# Chime_PCB_v2_8_11_17.net
KiCad netlist of a schematic drawn in EAGLE
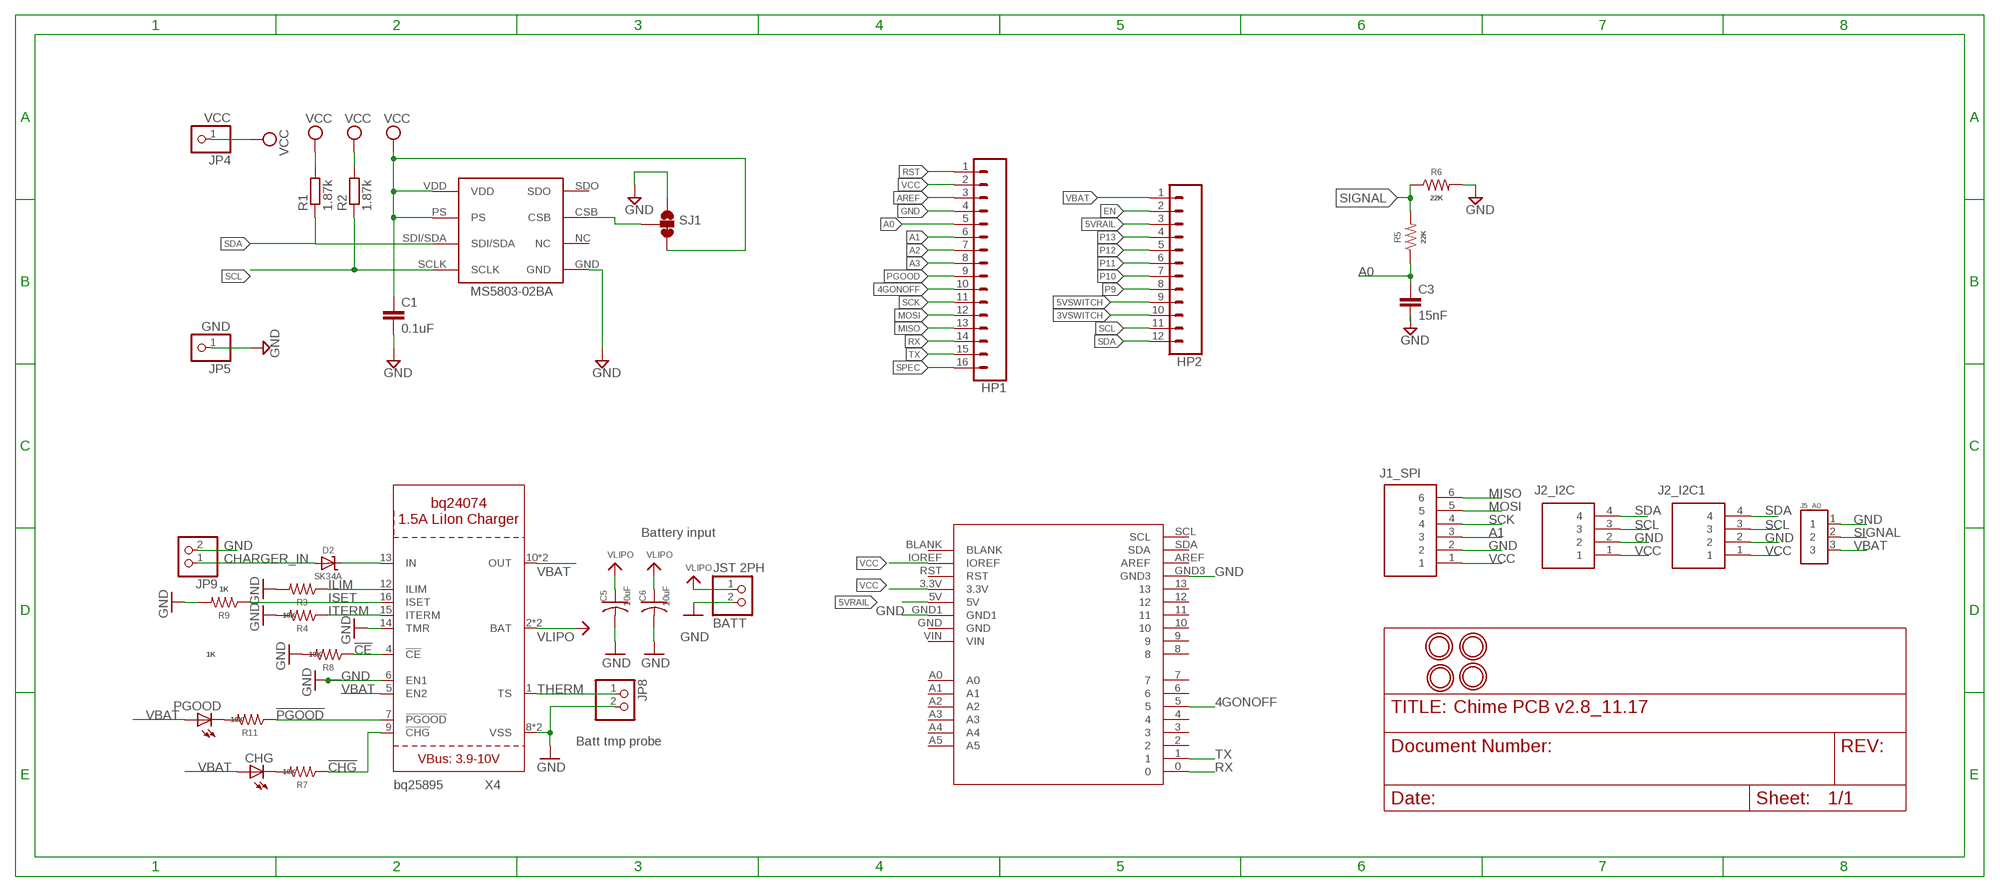
[diagram p0: schematic, sheet 1]

(export (version "E")
  (design (tool "Eeschema 10.0.6"))
  (components
    (comp (ref "BATT")
      (value "JST 2PH")
      (footprint "eagle-import:JST-PH-2-SMT-RA")
      (libsource (lib "eagle-import") (part "JST_2PIN-SMT-RA"))
    )
    (comp (ref "C1")
      (value "0.1uF")
      (footprint "eagle-import:C0805")
      (libsource (lib "eagle-import") (part "C-EUC0805"))
    )
    (comp (ref "C3")
      (value "15nF")
      (footprint "eagle-import:C0805")
      (libsource (lib "eagle-import") (part "C-EUC0805"))
    )
    (comp (ref "C5")
      (value "10uF")
      (footprint "eagle-import:C0805K")
      (libsource (lib "eagle-import") (part "C-USC0805K"))
    )
    (comp (ref "C6")
      (value "10uF")
      (footprint "eagle-import:C0805K")
      (libsource (lib "eagle-import") (part "C-USC0805K"))
    )
    (comp (ref "CHG")
      (value "LEDCHIPLED_0805")
      (footprint "eagle-import:CHIPLED_0805")
      (libsource (lib "eagle-import") (part "LEDCHIPLED_0805"))
    )
    (comp (ref "D2")
      (value "SK34A")
      (footprint "eagle-import:SMADIODE")
      (libsource (lib "eagle-import") (part "DIODE-SCHOTTKYSMA"))
    )
    (comp (ref "HP1")
      (value "CONN_16")
      (footprint "eagle-import:1X16")
      (libsource (lib "eagle-import") (part "CONN_16"))
    )
    (comp (ref "HP2")
      (value "CONN_12")
      (footprint "eagle-import:1X12")
      (libsource (lib "eagle-import") (part "CONN_12"))
    )
    (comp (ref "J1_SPI")
      (value "1725698")
      (footprint "eagle-import:1725698")
      (fields (field (name "MOUSER_PART_NUMBER") "651-1725698"))
      (libsource (lib "eagle-import") (part "1725698"))
    )
    (comp (ref "J2_I2C")
      (value "1725672")
      (footprint "eagle-import:1725672")
      (fields (field (name "MOUSER_PART_NUMBER") "651-1725672"))
      (libsource (lib "eagle-import") (part "1725672"))
    )
    (comp (ref "J2_I2C1")
      (value "1725672")
      (footprint "eagle-import:1725672")
      (fields (field (name "MOUSER_PART_NUMBER") "651-1725672"))
      (libsource (lib "eagle-import") (part "1725672"))
    )
    (comp (ref "J5_A0")
      (value "282834-3")
      (footprint "eagle-import:TE_282834-3")
      (fields (field (name "MF") "TE Connectivity"))
      (libsource (lib "eagle-import") (part "282834-3"))
    )
    (comp (ref "JP4")
      (value "VCC")
      (footprint "eagle-import:1X01")
      (libsource (lib "eagle-import") (part "PINHD-1X1"))
    )
    (comp (ref "JP5")
      (value "GND")
      (footprint "eagle-import:1X01")
      (libsource (lib "eagle-import") (part "PINHD-1X1"))
    )
    (comp (ref "JP8")
      (value "PINHD-1X2")
      (footprint "eagle-import:1X02")
      (libsource (lib "eagle-import") (part "PINHD-1X2"))
    )
    (comp (ref "JP9")
      (value "PINHD-1X2")
      (footprint "eagle-import:1X02")
      (libsource (lib "eagle-import") (part "PINHD-1X2"))
    )
    (comp (ref "PGOOD")
      (value "PGOOD")
      (footprint "eagle-import:CHIPLED_0805")
      (libsource (lib "eagle-import") (part "LEDCHIPLED_0805"))
    )
    (comp (ref "R1")
      (value "1.87k")
      (footprint "eagle-import:R0805")
      (libsource (lib "eagle-import") (part "R-EU_R0805"))
    )
    (comp (ref "R2")
      (value "1.87k")
      (footprint "eagle-import:R0805")
      (libsource (lib "eagle-import") (part "R-EU_R0805"))
    )
    (comp (ref "R3")
      (value "1K")
      (footprint "eagle-import:M0805")
      (libsource (lib "eagle-import") (part "R-US_M0805"))
    )
    (comp (ref "R4")
      (value "10K")
      (footprint "eagle-import:M0805")
      (libsource (lib "eagle-import") (part "R-US_M0805"))
    )
    (comp (ref "R5")
      (value "22K")
      (footprint "eagle-import:M0805")
      (libsource (lib "eagle-import") (part "R-US_M0805"))
    )
    (comp (ref "R6")
      (value "22K")
      (footprint "eagle-import:M0805")
      (libsource (lib "eagle-import") (part "R-US_M0805"))
    )
    (comp (ref "R7")
      (value "10K")
      (footprint "eagle-import:M0805")
      (libsource (lib "eagle-import") (part "R-US_M0805"))
    )
    (comp (ref "R8")
      (value "10K")
      (footprint "eagle-import:M0805")
      (libsource (lib "eagle-import") (part "R-US_M0805"))
    )
    (comp (ref "R9")
      (value "1K")
      (footprint "eagle-import:M0805")
      (libsource (lib "eagle-import") (part "R-US_M0805"))
    )
    (comp (ref "R11")
      (value "10K")
      (footprint "eagle-import:M0805")
      (libsource (lib "eagle-import") (part "R-US_M0805"))
    )
    (comp (ref "SJ1")
      (value "JUMPER-SMT_3_1-NC_TRACE_SILK")
      (footprint "eagle-import:SMT-JUMPER_3_1-NC_TRACE_SILK")
      (libsource (lib "eagle-import") (part "JUMPER-SMT_3_1-NC_TRACE_SILK"))
    )
    (comp (ref "U$1")
      (value "LTE_BOARD")
      (footprint "eagle-import:LTE_BOARD_FOOTPRINT")
      (libsource (lib "eagle-import") (part "LTE_BOARD"))
    )
    (comp (ref "U$2")
      (value "MOUNTINGHOLE2.5")
      (footprint "eagle-import:MOUNTINGHOLE_2.5_PLATED")
      (libsource (lib "eagle-import") (part "MOUNTINGHOLE2.5"))
    )
    (comp (ref "U$3")
      (value "MOUNTINGHOLE2.5")
      (footprint "eagle-import:MOUNTINGHOLE_2.5_PLATED")
      (libsource (lib "eagle-import") (part "MOUNTINGHOLE2.5"))
    )
    (comp (ref "U$4")
      (value "MOUNTINGHOLE2.5")
      (footprint "eagle-import:MOUNTINGHOLE_2.5_PLATED")
      (libsource (lib "eagle-import") (part "MOUNTINGHOLE2.5"))
    )
    (comp (ref "U$5")
      (value "MOUNTINGHOLE2.5")
      (footprint "eagle-import:MOUNTINGHOLE_2.5_PLATED")
      (libsource (lib "eagle-import") (part "MOUNTINGHOLE2.5"))
    )
    (comp (ref "U1")
      (value "MS5803-02BA")
      (footprint "eagle-import:MS5803-02BA")
      (libsource (lib "eagle-import") (part "MS5803-02BA"))
    )
    (comp (ref "X4")
      (value "BQ24074")
      (footprint "eagle-import:QFN16_3MM")
      (libsource (lib "eagle-import") (part "BQ24074"))
    )
  )
  (nets
    (net (code "1") (name "/CHARGER_IN") (class "Default")
      (node (ref "D2") (pin "A") (pinfunction "A_A") (pintype "passive"))
      (node (ref "JP9") (pin "1") (pinfunction "1_1") (pintype "passive"))
    )
    (net (code "2") (name "/ILIM") (class "Default")
      (node (ref "R3") (pin "1") (pinfunction "1_1") (pintype "passive"))
      (node (ref "X4") (pin "12") (pinfunction "ILIM_12") (pintype "input"))
    )
    (net (code "3") (name "/ISET") (class "Default")
      (node (ref "R9") (pin "1") (pinfunction "1_1") (pintype "passive"))
      (node (ref "X4") (pin "16") (pinfunction "ISET_16") (pintype "input"))
    )
    (net (code "4") (name "/ITERM") (class "Default")
      (node (ref "R4") (pin "1") (pinfunction "1_1") (pintype "passive"))
      (node (ref "X4") (pin "15") (pinfunction "ITERM_15") (pintype "input"))
    )
    (net (code "5") (name "/THERM") (class "Default")
      (node (ref "JP8") (pin "1") (pinfunction "1_1") (pintype "passive"))
      (node (ref "X4") (pin "1") (pinfunction "TS_1") (pintype "input"))
    )
    (net (code "6") (name "/~{CE}") (class "Default")
      (node (ref "R8") (pin "1") (pinfunction "1_1") (pintype "passive"))
      (node (ref "X4") (pin "4") (pinfunction "~{CE}_4") (pintype "input"))
    )
    (net (code "7") (name "/~{CHG}") (class "Default")
      (node (ref "R7") (pin "1") (pinfunction "1_1") (pintype "passive"))
      (node (ref "X4") (pin "9") (pinfunction "~{CHG}_9") (pintype "output"))
    )
    (net (code "8") (name "/~{PGOOD}") (class "Default")
      (node (ref "R11") (pin "1") (pinfunction "1_1") (pintype "passive"))
      (node (ref "X4") (pin "7") (pinfunction "~{PGOOD}_7") (pintype "output"))
    )
    (net (code "9") (name "3VSWITCH") (class "Default")
      (node (ref "HP2") (pin "10") (pinfunction "10_10") (pintype "passive"))
    )
    (net (code "10") (name "4GONOFF") (class "Default")
      (node (ref "HP1") (pin "10") (pinfunction "10_10") (pintype "passive"))
      (node (ref "U$1") (pin "5") (pinfunction "5_5") (pintype "bidirectional"))
    )
    (net (code "11") (name "5VRAIL") (class "Default")
      (node (ref "HP2") (pin "3") (pinfunction "3_3") (pintype "passive"))
      (node (ref "U$1") (pin "5V") (pinfunction "5V_5V") (pintype "bidirectional"))
    )
    (net (code "12") (name "5VSWITCH") (class "Default")
      (node (ref "HP2") (pin "9") (pinfunction "9_9") (pintype "passive"))
    )
    (net (code "13") (name "A0") (class "Default")
      (node (ref "C3") (pin "1") (pinfunction "1_1") (pintype "passive"))
      (node (ref "HP1") (pin "5") (pinfunction "5_5") (pintype "passive"))
      (node (ref "R5") (pin "1") (pinfunction "1_1") (pintype "passive"))
    )
    (net (code "14") (name "A1") (class "Default")
      (node (ref "HP1") (pin "6") (pinfunction "6_6") (pintype "passive"))
      (node (ref "J1_SPI") (pin "3") (pinfunction "3_3") (pintype "bidirectional"))
    )
    (net (code "15") (name "A2") (class "Default")
      (node (ref "HP1") (pin "7") (pinfunction "7_7") (pintype "passive"))
    )
    (net (code "16") (name "A3") (class "Default")
      (node (ref "HP1") (pin "8") (pinfunction "8_8") (pintype "passive"))
    )
    (net (code "17") (name "AREF") (class "Default")
      (node (ref "HP1") (pin "3") (pinfunction "3_3") (pintype "passive"))
    )
    (net (code "18") (name "EN") (class "Default")
      (node (ref "HP2") (pin "2") (pinfunction "2_2") (pintype "passive"))
    )
    (net (code "19") (name "GND") (class "Default")
      (node (ref "BATT") (pin "2") (pinfunction "1_2") (pintype "passive"))
      (node (ref "C1") (pin "2") (pinfunction "2_2") (pintype "passive"))
      (node (ref "C3") (pin "2") (pinfunction "2_2") (pintype "passive"))
      (node (ref "C5") (pin "2") (pinfunction "2_2") (pintype "passive"))
      (node (ref "C6") (pin "2") (pinfunction "2_2") (pintype "passive"))
      (node (ref "HP1") (pin "4") (pinfunction "4_4") (pintype "passive"))
      (node (ref "J1_SPI") (pin "2") (pinfunction "2_2") (pintype "bidirectional"))
      (node (ref "J2_I2C") (pin "2") (pinfunction "2_2") (pintype "bidirectional"))
      (node (ref "J2_I2C1") (pin "2") (pinfunction "2_2") (pintype "bidirectional"))
      (node (ref "J5_A0") (pin "1") (pinfunction "1_1") (pintype "passive"))
      (node (ref "JP5") (pin "1") (pinfunction "1_1") (pintype "passive"))
      (node (ref "JP8") (pin "2") (pinfunction "2_2") (pintype "passive"))
      (node (ref "JP9") (pin "2") (pinfunction "2_2") (pintype "passive"))
      (node (ref "R3") (pin "2") (pinfunction "2_2") (pintype "passive"))
      (node (ref "R4") (pin "2") (pinfunction "2_2") (pintype "passive"))
      (node (ref "R6") (pin "2") (pinfunction "2_2") (pintype "passive"))
      (node (ref "R8") (pin "2") (pinfunction "2_2") (pintype "passive"))
      (node (ref "R9") (pin "2") (pinfunction "2_2") (pintype "passive"))
      (node (ref "SJ1") (pin "1") (pinfunction "1_1") (pintype "passive"))
      (node (ref "U$1") (pin "GND1") (pinfunction "GND1_GND1") (pintype "bidirectional"))
      (node (ref "U$1") (pin "GND3") (pinfunction "GND3_GND3") (pintype "bidirectional"))
      (node (ref "U1") (pin "GND") (pinfunction "GND_GND") (pintype "bidirectional"))
      (node (ref "X4") (pin "14") (pinfunction "TMR_14") (pintype "input"))
      (node (ref "X4") (pin "6") (pinfunction "EN1_6") (pintype "input"))
      (node (ref "X4") (pin "8") (pinfunction "VSS_8") (pintype "power_in"))
      (node (ref "X4") (pin "THERMAL") (pinfunction "VSS_THERMAL") (pintype "power_in"))
    )
    (net (code "20") (name "MISO") (class "Default")
      (node (ref "HP1") (pin "13") (pinfunction "13_13") (pintype "passive"))
      (node (ref "J1_SPI") (pin "6") (pinfunction "6_6") (pintype "bidirectional"))
    )
    (net (code "21") (name "MOSI") (class "Default")
      (node (ref "HP1") (pin "12") (pinfunction "12_12") (pintype "passive"))
      (node (ref "J1_SPI") (pin "5") (pinfunction "5_5") (pintype "bidirectional"))
    )
    (net (code "22") (name "Net-(CHG-PadC)") (class "Default")
      (node (ref "CHG") (pin "C") (pinfunction "C_C") (pintype "passive"))
      (node (ref "R7") (pin "2") (pinfunction "2_2") (pintype "passive"))
    )
    (net (code "23") (name "Net-(PGOOD-PadC)") (class "Default")
      (node (ref "PGOOD") (pin "C") (pinfunction "C_C") (pintype "passive"))
      (node (ref "R11") (pin "2") (pinfunction "2_2") (pintype "passive"))
    )
    (net (code "24") (name "Net-(SJ1-Pad2)") (class "Default")
      (node (ref "SJ1") (pin "2") (pinfunction "2_2") (pintype "passive"))
      (node (ref "U1") (pin "CSB") (pinfunction "CSB_CSB") (pintype "bidirectional"))
    )
    (net (code "25") (name "Net-(X4-IN)") (class "Default")
      (node (ref "D2") (pin "C") (pinfunction "C_C") (pintype "passive"))
      (node (ref "X4") (pin "13") (pinfunction "IN_13") (pintype "power_in"))
    )
    (net (code "26") (name "P9") (class "Default")
      (node (ref "HP2") (pin "8") (pinfunction "8_8") (pintype "passive"))
    )
    (net (code "27") (name "P10") (class "Default")
      (node (ref "HP2") (pin "7") (pinfunction "7_7") (pintype "passive"))
    )
    (net (code "28") (name "P11") (class "Default")
      (node (ref "HP2") (pin "6") (pinfunction "6_6") (pintype "passive"))
    )
    (net (code "29") (name "P12") (class "Default")
      (node (ref "HP2") (pin "5") (pinfunction "5_5") (pintype "passive"))
    )
    (net (code "30") (name "P13") (class "Default")
      (node (ref "HP2") (pin "4") (pinfunction "4_4") (pintype "passive"))
    )
    (net (code "31") (name "PGOOD") (class "Default")
      (node (ref "HP1") (pin "9") (pinfunction "9_9") (pintype "passive"))
    )
    (net (code "32") (name "RST") (class "Default")
      (node (ref "HP1") (pin "1") (pinfunction "1_1") (pintype "passive"))
    )
    (net (code "33") (name "RX") (class "Default")
      (node (ref "HP1") (pin "14") (pinfunction "14_14") (pintype "passive"))
      (node (ref "U$1") (pin "0") (pinfunction "0_0") (pintype "bidirectional"))
    )
    (net (code "34") (name "SCK") (class "Default")
      (node (ref "HP1") (pin "11") (pinfunction "11_11") (pintype "passive"))
      (node (ref "J1_SPI") (pin "4") (pinfunction "4_4") (pintype "bidirectional"))
    )
    (net (code "35") (name "SCL") (class "Default")
      (node (ref "HP2") (pin "11") (pinfunction "11_11") (pintype "passive"))
      (node (ref "J2_I2C") (pin "3") (pinfunction "3_3") (pintype "bidirectional"))
      (node (ref "J2_I2C1") (pin "3") (pinfunction "3_3") (pintype "bidirectional"))
      (node (ref "R2") (pin "1") (pinfunction "1_1") (pintype "passive"))
      (node (ref "U1") (pin "SCLK") (pinfunction "SCLK_SCLK") (pintype "bidirectional"))
    )
    (net (code "36") (name "SDA") (class "Default")
      (node (ref "HP2") (pin "12") (pinfunction "12_12") (pintype "passive"))
      (node (ref "J2_I2C") (pin "4") (pinfunction "4_4") (pintype "bidirectional"))
      (node (ref "J2_I2C1") (pin "4") (pinfunction "4_4") (pintype "bidirectional"))
      (node (ref "R1") (pin "1") (pinfunction "1_1") (pintype "passive"))
      (node (ref "U1") (pin "SDI/SDA") (pinfunction "SDI/SDA_SDI/SDA") (pintype "bidirectional"))
    )
    (net (code "37") (name "SIGNAL") (class "Default")
      (node (ref "J5_A0") (pin "2") (pinfunction "2_2") (pintype "passive"))
      (node (ref "R5") (pin "2") (pinfunction "2_2") (pintype "passive"))
      (node (ref "R6") (pin "1") (pinfunction "1_1") (pintype "passive"))
    )
    (net (code "38") (name "SPEC") (class "Default")
      (node (ref "HP1") (pin "16") (pinfunction "16_16") (pintype "passive"))
    )
    (net (code "39") (name "TX") (class "Default")
      (node (ref "HP1") (pin "15") (pinfunction "15_15") (pintype "passive"))
      (node (ref "U$1") (pin "1") (pinfunction "1_1") (pintype "bidirectional"))
    )
    (net (code "40") (name "VBAT") (class "Default")
      (node (ref "CHG") (pin "A") (pinfunction "A_A") (pintype "passive"))
      (node (ref "HP2") (pin "1") (pinfunction "1_1") (pintype "passive"))
      (node (ref "J5_A0") (pin "3") (pinfunction "3_3") (pintype "passive"))
      (node (ref "PGOOD") (pin "A") (pinfunction "A_A") (pintype "passive"))
      (node (ref "X4") (pin "10") (pinfunction "OUT_10") (pintype "output"))
      (node (ref "X4") (pin "11") (pinfunction "OUT_11") (pintype "output"))
      (node (ref "X4") (pin "5") (pinfunction "EN2_5") (pintype "input"))
    )
    (net (code "41") (name "VCC") (class "Default")
      (node (ref "C1") (pin "1") (pinfunction "1_1") (pintype "passive"))
      (node (ref "HP1") (pin "2") (pinfunction "2_2") (pintype "passive"))
      (node (ref "J1_SPI") (pin "1") (pinfunction "1_1") (pintype "bidirectional"))
      (node (ref "J2_I2C") (pin "1") (pinfunction "1_1") (pintype "bidirectional"))
      (node (ref "J2_I2C1") (pin "1") (pinfunction "1_1") (pintype "bidirectional"))
      (node (ref "JP4") (pin "1") (pinfunction "1_1") (pintype "passive"))
      (node (ref "R1") (pin "2") (pinfunction "2_2") (pintype "passive"))
      (node (ref "R2") (pin "2") (pinfunction "2_2") (pintype "passive"))
      (node (ref "SJ1") (pin "3") (pinfunction "3_3") (pintype "passive"))
      (node (ref "U$1") (pin "3.3V") (pinfunction "3.3V_3.3V") (pintype "bidirectional"))
      (node (ref "U$1") (pin "IOREF") (pinfunction "IOREF_IOREF") (pintype "bidirectional"))
      (node (ref "U1") (pin "PS") (pinfunction "PS_PS") (pintype "bidirectional"))
      (node (ref "U1") (pin "VDD") (pinfunction "VDD_VDD") (pintype "bidirectional"))
    )
    (net (code "42") (name "VLIPO") (class "Default")
      (node (ref "BATT") (pin "1") (pinfunction "2_1") (pintype "passive"))
      (node (ref "C5") (pin "1") (pinfunction "1_1") (pintype "passive"))
      (node (ref "C6") (pin "1") (pinfunction "1_1") (pintype "passive"))
      (node (ref "X4") (pin "2") (pinfunction "BAT_2") (pintype "input"))
      (node (ref "X4") (pin "3") (pinfunction "BAT_3") (pintype "input"))
    )
    (net (code "43") (name "unconnected-(U$1-Pad2)") (class "Default")
      (node (ref "U$1") (pin "2") (pinfunction "2_2") (pintype "bidirectional"))
    )
    (net (code "44") (name "unconnected-(U$1-Pad3)") (class "Default")
      (node (ref "U$1") (pin "3") (pinfunction "3_3") (pintype "bidirectional"))
    )
    (net (code "45") (name "unconnected-(U$1-Pad4)") (class "Default")
      (node (ref "U$1") (pin "4") (pinfunction "4_4") (pintype "bidirectional"))
    )
    (net (code "46") (name "unconnected-(U$1-Pad6)") (class "Default")
      (node (ref "U$1") (pin "6") (pinfunction "6_6") (pintype "bidirectional"))
    )
    (net (code "47") (name "unconnected-(U$1-Pad7)") (class "Default")
      (node (ref "U$1") (pin "7") (pinfunction "7_7") (pintype "bidirectional"))
    )
    (net (code "48") (name "unconnected-(U$1-Pad8)") (class "Default")
      (node (ref "U$1") (pin "8") (pinfunction "8_8") (pintype "bidirectional"))
    )
    (net (code "49") (name "unconnected-(U$1-Pad9)") (class "Default")
      (node (ref "U$1") (pin "9") (pinfunction "9_9") (pintype "bidirectional"))
    )
    (net (code "50") (name "unconnected-(U$1-Pad10)") (class "Default")
      (node (ref "U$1") (pin "10") (pinfunction "10_10") (pintype "bidirectional"))
    )
    (net (code "51") (name "unconnected-(U$1-Pad11)") (class "Default")
      (node (ref "U$1") (pin "11") (pinfunction "11_11") (pintype "bidirectional"))
    )
    (net (code "52") (name "unconnected-(U$1-Pad12)") (class "Default")
      (node (ref "U$1") (pin "12") (pinfunction "12_12") (pintype "bidirectional"))
    )
    (net (code "53") (name "unconnected-(U$1-Pad13)") (class "Default")
      (node (ref "U$1") (pin "13") (pinfunction "13_13") (pintype "bidirectional"))
    )
    (net (code "54") (name "unconnected-(U$1-PadA0)") (class "Default")
      (node (ref "U$1") (pin "A0") (pinfunction "A0_A0") (pintype "bidirectional"))
    )
    (net (code "55") (name "unconnected-(U$1-PadA1)") (class "Default")
      (node (ref "U$1") (pin "A1") (pinfunction "A1_A1") (pintype "bidirectional"))
    )
    (net (code "56") (name "unconnected-(U$1-PadA2)") (class "Default")
      (node (ref "U$1") (pin "A2") (pinfunction "A2_A2") (pintype "bidirectional"))
    )
    (net (code "57") (name "unconnected-(U$1-PadA3)") (class "Default")
      (node (ref "U$1") (pin "A3") (pinfunction "A3_A3") (pintype "bidirectional"))
    )
    (net (code "58") (name "unconnected-(U$1-PadA4)") (class "Default")
      (node (ref "U$1") (pin "A4") (pinfunction "A4_A4") (pintype "bidirectional"))
    )
    (net (code "59") (name "unconnected-(U$1-PadA5)") (class "Default")
      (node (ref "U$1") (pin "A5") (pinfunction "A5_A5") (pintype "bidirectional"))
    )
    (net (code "60") (name "unconnected-(U$1-PadAREF)") (class "Default")
      (node (ref "U$1") (pin "AREF") (pinfunction "AREF_AREF") (pintype "bidirectional"))
    )
    (net (code "61") (name "unconnected-(U$1-PadBLANK)") (class "Default")
      (node (ref "U$1") (pin "BLANK") (pinfunction "BLANK_BLANK") (pintype "bidirectional"))
    )
    (net (code "62") (name "unconnected-(U$1-PadGND)") (class "Default")
      (node (ref "U$1") (pin "GND") (pinfunction "GND_GND") (pintype "bidirectional"))
    )
    (net (code "63") (name "unconnected-(U$1-PadRST)") (class "Default")
      (node (ref "U$1") (pin "RST") (pinfunction "RST_RST") (pintype "bidirectional"))
    )
    (net (code "64") (name "unconnected-(U$1-PadSCL)") (class "Default")
      (node (ref "U$1") (pin "SCL") (pinfunction "SCL_SCL") (pintype "bidirectional"))
    )
    (net (code "65") (name "unconnected-(U$1-PadSDA)") (class "Default")
      (node (ref "U$1") (pin "SDA") (pinfunction "SDA_SDA") (pintype "bidirectional"))
    )
    (net (code "66") (name "unconnected-(U$1-PadVIN)") (class "Default")
      (node (ref "U$1") (pin "VIN") (pinfunction "VIN_VIN") (pintype "bidirectional"))
    )
    (net (code "67") (name "unconnected-(U1-PadNC)") (class "Default")
      (node (ref "U1") (pin "NC") (pinfunction "NC_NC") (pintype "bidirectional"))
    )
    (net (code "68") (name "unconnected-(U1-PadSDO)") (class "Default")
      (node (ref "U1") (pin "SDO") (pinfunction "SDO_SDO") (pintype "bidirectional"))
    )
  )
)
